# sensor_board_v0_53.net
KiCad netlist of a schematic drawn in EAGLE
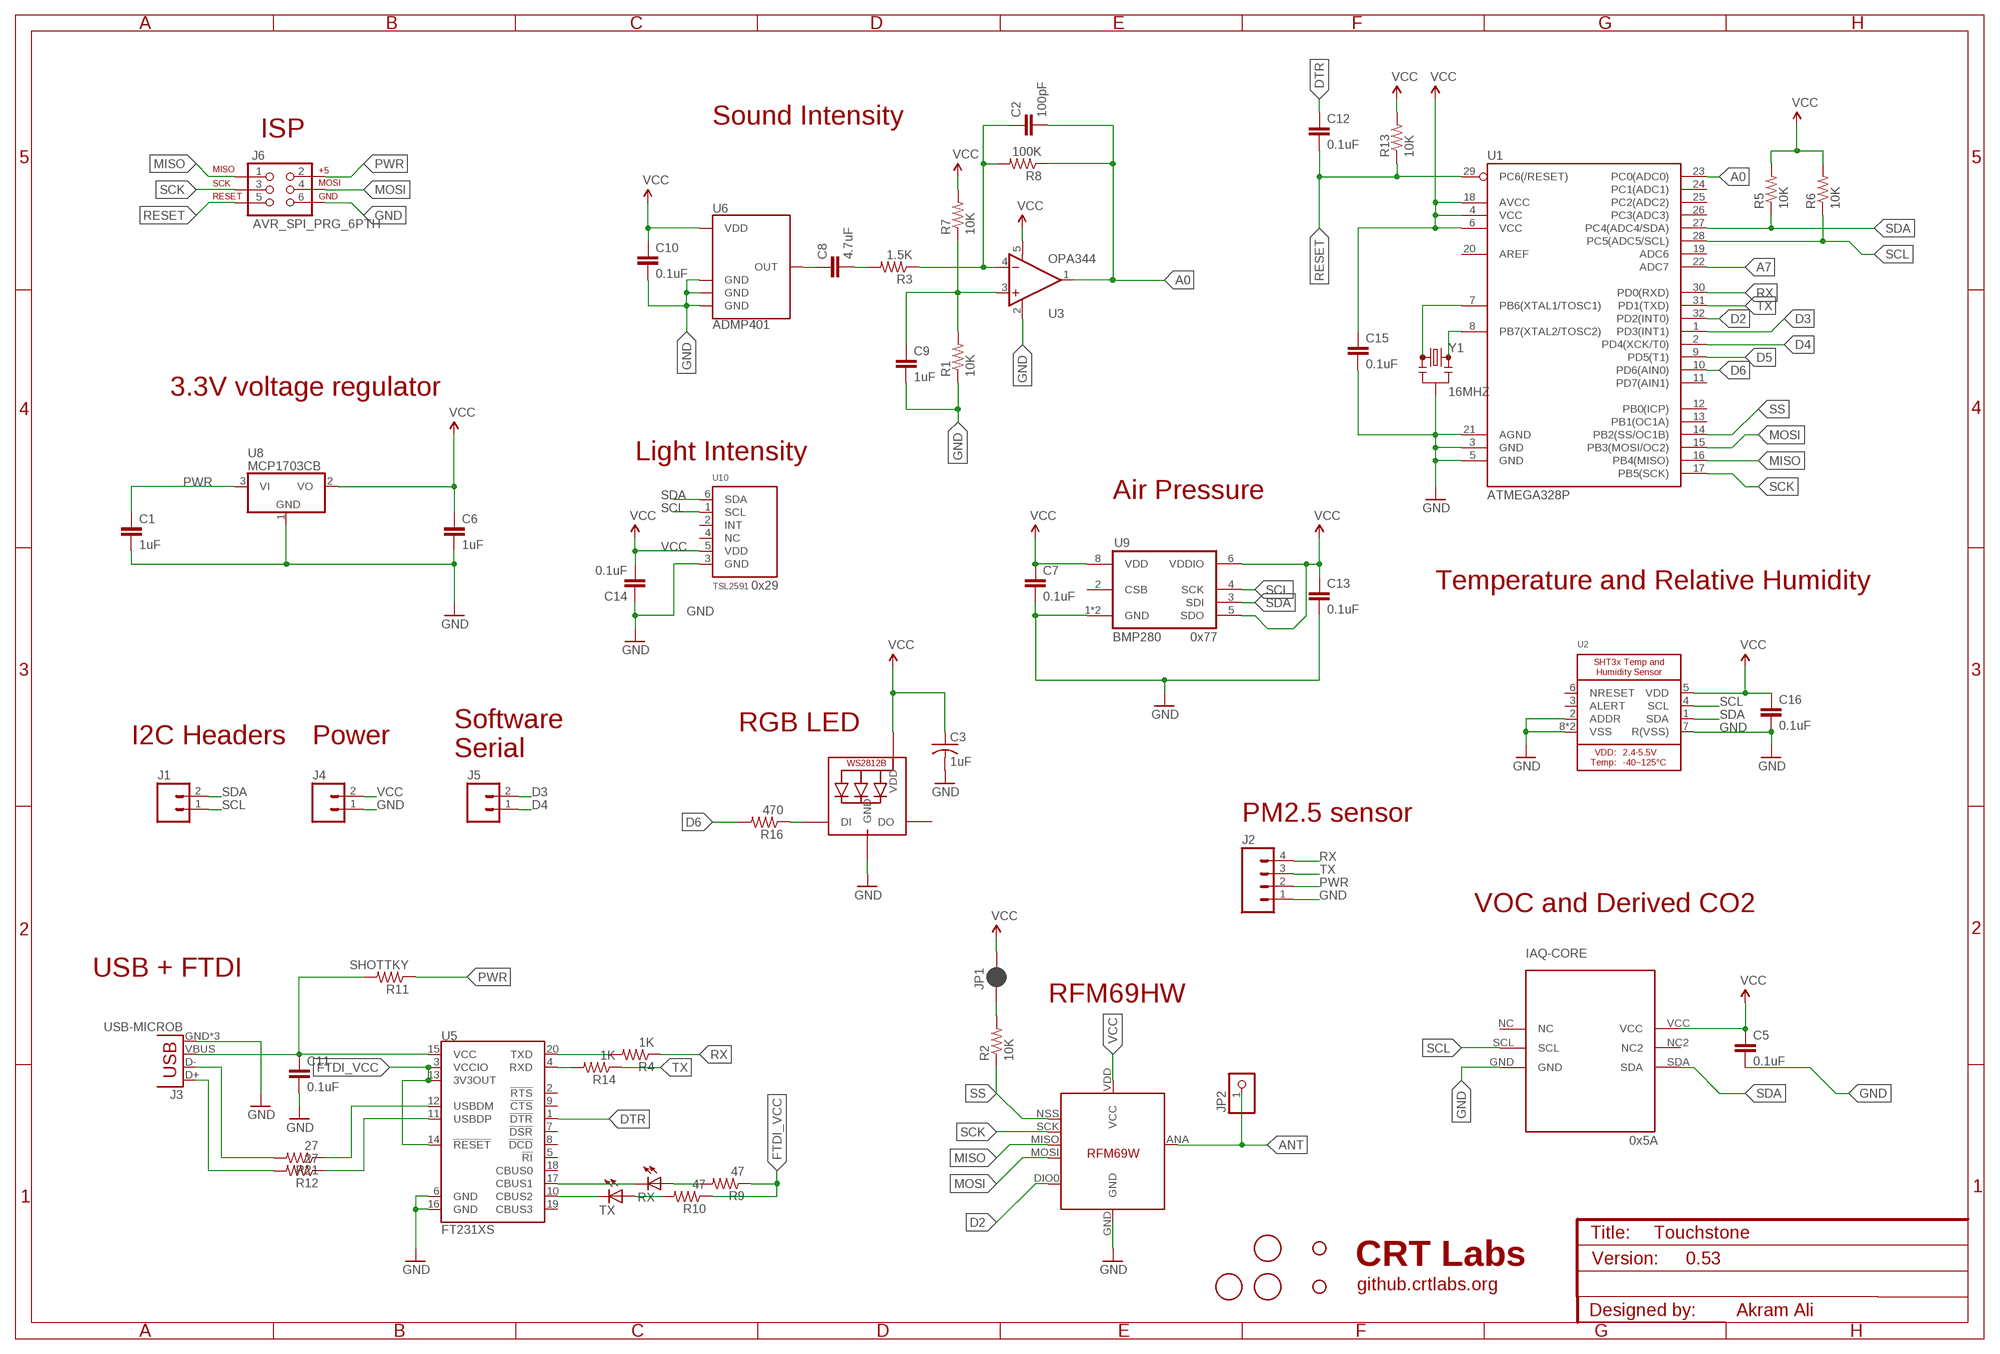
[diagram p0: schematic, sheet 1]

(export (version "E")
  (design (tool "Eeschema 10.0.6"))
  (components
    (comp (ref "C1")
      (value "1uF")
      (footprint "eagle-import:0805")
      (fields (field (name "MPN") "CC0805ZRY5V8BB105"))
      (libsource (lib "eagle-import") (part "CAP0805"))
    )
    (comp (ref "C2")
      (value "100pF")
      (footprint "eagle-import:0805")
      (fields (field (name "MPN") "CC0805JRNPOABN101"))
      (libsource (lib "eagle-import") (part "CAP0805"))
    )
    (comp (ref "C3")
      (value "1uF")
      (footprint "eagle-import:C0603K")
      (fields (field (name "MPN") "CC0805ZRY5V8BB105"))
      (libsource (lib "eagle-import") (part "C-USC0603K"))
    )
    (comp (ref "C5")
      (value "0.1uF")
      (footprint "eagle-import:0805")
      (fields (field (name "MPN") "CC0805KRX7R9BB104"))
      (libsource (lib "eagle-import") (part "SparkFun-Passives_CAP0805"))
    )
    (comp (ref "C6")
      (value "1uF")
      (footprint "eagle-import:0805")
      (fields (field (name "MPN") "CC0805ZRY5V8BB105"))
      (libsource (lib "eagle-import") (part "CAP0805"))
    )
    (comp (ref "C7")
      (value "0.1uF")
      (footprint "eagle-import:0805")
      (fields (field (name "MPN") "CC0805KRX7R9BB104"))
      (libsource (lib "eagle-import") (part "SparkFun-Passives_CAP0805"))
    )
    (comp (ref "C8")
      (value "4.7uF")
      (footprint "eagle-import:0805")
      (fields (field (name "MPN") "CC0805KKX7R6BB475"))
      (libsource (lib "eagle-import") (part "CAP0805"))
    )
    (comp (ref "C9")
      (value "1uF")
      (footprint "eagle-import:0805")
      (fields (field (name "MPN") "CC0805ZRY5V8BB105"))
      (libsource (lib "eagle-import") (part "CAP0805"))
    )
    (comp (ref "C10")
      (value "0.1uF")
      (footprint "eagle-import:0805")
      (fields (field (name "MPN") "CC0805KRX7R9BB104"))
      (libsource (lib "eagle-import") (part "CAP0805"))
    )
    (comp (ref "C11")
      (value "0.1uF")
      (footprint "eagle-import:0805")
      (fields (field (name "MPN") "CC0805KRX7R9BB104"))
      (libsource (lib "eagle-import") (part "CAP0805"))
    )
    (comp (ref "C12")
      (value "0.1uF")
      (footprint "eagle-import:0805")
      (fields (field (name "MPN") "CC0805KRX7R9BB104"))
      (libsource (lib "eagle-import") (part "SparkFun-Passives_CAP0805"))
    )
    (comp (ref "C13")
      (value "0.1uF")
      (footprint "eagle-import:0805")
      (fields (field (name "MPN") "CC0805KRX7R9BB104"))
      (libsource (lib "eagle-import") (part "SparkFun-Passives_CAP0805"))
    )
    (comp (ref "C14")
      (value "0.1uF")
      (footprint "eagle-import:0805")
      (fields (field (name "MPN") "CC0805KRX7R9BB104"))
      (libsource (lib "eagle-import") (part "SparkFun-Passives_CAP0805"))
    )
    (comp (ref "C15")
      (value "0.1uF")
      (footprint "eagle-import:0805")
      (fields (field (name "MPN") "CC0805KRX7R9BB104"))
      (libsource (lib "eagle-import") (part "SparkFun-Passives_CAP0805"))
    )
    (comp (ref "C16")
      (value "0.1uF")
      (footprint "eagle-import:0805")
      (fields (field (name "MPN") "CC0805KRX7R9BB104"))
      (libsource (lib "eagle-import") (part "SparkFun-Passives_CAP0805"))
    )
    (comp (ref "H1")
      (value "STAND-OFF")
      (footprint "eagle-import:STAND-OFF")
      (libsource (lib "eagle-import") (part "STAND-OFF"))
    )
    (comp (ref "H2")
      (value "STAND-OFF")
      (footprint "eagle-import:STAND-OFF")
      (libsource (lib "eagle-import") (part "STAND-OFF"))
    )
    (comp (ref "IAQ-CORE")
      (value "IAQ-CORE")
      (footprint "eagle-import:IAQ-CORE")
      (fields (field (name "MPN") "IAQ-CORE C"))
      (libsource (lib "eagle-import") (part "IAQ-CORE"))
    )
    (comp (ref "J1")
      (value "M02PTH")
      (footprint "eagle-import:1X02")
      (libsource (lib "eagle-import") (part "M02PTH"))
    )
    (comp (ref "J2")
      (value "M04PTH")
      (footprint "eagle-import:1X04")
      (libsource (lib "eagle-import") (part "M04PTH"))
    )
    (comp (ref "J3")
      (value "USB-MICROB")
      (footprint "eagle-import:USB-MICROB")
      (fields (field (name "MPN") "47346-0001"))
      (libsource (lib "eagle-import") (part "USB-MICROB"))
    )
    (comp (ref "J4")
      (value "M02PTH")
      (footprint "eagle-import:1X02")
      (libsource (lib "eagle-import") (part "M02PTH"))
    )
    (comp (ref "J5")
      (value "M02PTH")
      (footprint "eagle-import:1X02")
      (libsource (lib "eagle-import") (part "M02PTH"))
    )
    (comp (ref "J6")
      (value "AVR_SPI_PRG_6PTH")
      (footprint "eagle-import:2X3")
      (libsource (lib "eagle-import") (part "AVR_SPI_PRG_6PTH"))
    )
    (comp (ref "JP1")
      (value "JUMPER-PAD-2-NC_BY_PASTEFULL-BOX-SILK")
      (footprint "eagle-import:PAD-JUMPER-2-NC_BY_PASTE_YES_SILK_FULL_BOX")
      (libsource (lib "eagle-import") (part "JUMPER-PAD-2-NC_BY_PASTEFULL-BOX-SILK"))
    )
    (comp (ref "JP2")
      (value "PINHD-1X1")
      (footprint "eagle-import:1X01")
      (libsource (lib "eagle-import") (part "PINHD-1X1"))
    )
    (comp (ref "LED1")
      (value "WS2812B3535")
      (footprint "eagle-import:LED3535")
      (fields (field (name "MPN") "SK6812 mini"))
      (libsource (lib "eagle-import") (part "WS2812B3535"))
    )
    (comp (ref "R1")
      (value "10K")
      (footprint "eagle-import:0805")
      (fields (field (name "MPN") "RC0805FR-0710KL"))
      (libsource (lib "eagle-import") (part "RESISTOR0805-RES"))
    )
    (comp (ref "R2")
      (value "10K")
      (footprint "eagle-import:0805")
      (fields (field (name "MPN") "RC0805FR-0710KL"))
      (libsource (lib "eagle-import") (part "RESISTOR0805-RES"))
    )
    (comp (ref "R3")
      (value "1.5K")
      (footprint "eagle-import:0805")
      (fields (field (name "MPN") "RC0805FR-071K5L "))
      (libsource (lib "eagle-import") (part "RESISTOR0805-RES"))
    )
    (comp (ref "R4")
      (value "1K")
      (footprint "eagle-import:0805")
      (fields (field (name "MPN") "RC0805FR-071KL"))
      (libsource (lib "eagle-import") (part "RESISTOR0805-RES"))
    )
    (comp (ref "R5")
      (value "10K")
      (footprint "eagle-import:0805")
      (fields (field (name "MPN") "RC0805FR-0710KL"))
      (libsource (lib "eagle-import") (part "SparkFun-Resistors_RESISTOR0805-RES"))
    )
    (comp (ref "R6")
      (value "10K")
      (footprint "eagle-import:0805")
      (fields (field (name "MPN") "RC0805FR-0710KL"))
      (libsource (lib "eagle-import") (part "SparkFun-Resistors_RESISTOR0805-RES"))
    )
    (comp (ref "R7")
      (value "10K")
      (footprint "eagle-import:0805")
      (fields (field (name "MPN") "RC0805FR-0710KL"))
      (libsource (lib "eagle-import") (part "RESISTOR0805-RES"))
    )
    (comp (ref "R8")
      (value "100K")
      (footprint "eagle-import:0805")
      (fields (field (name "MPN") "RC0805FR-07100KL "))
      (libsource (lib "eagle-import") (part "RESISTOR0805-RES"))
    )
    (comp (ref "R9")
      (value "47")
      (footprint "eagle-import:0805")
      (fields (field (name "MPN") "RC0805FR-0747RL "))
      (libsource (lib "eagle-import") (part "RESISTOR0805-RES"))
    )
    (comp (ref "R10")
      (value "47")
      (footprint "eagle-import:0805")
      (fields (field (name "MPN") "RC0805FR-0747RL "))
      (libsource (lib "eagle-import") (part "RESISTOR0805-RES"))
    )
    (comp (ref "R11")
      (value "SHOTTKY")
      (footprint "eagle-import:0805")
      (fields (field (name "MPN") "SD0805S040S0R5"))
      (libsource (lib "eagle-import") (part "RESISTOR0805-RES"))
    )
    (comp (ref "R12")
      (value "27")
      (footprint "eagle-import:0805")
      (fields (field (name "MPN") "RC0805FR-0727RL "))
      (libsource (lib "eagle-import") (part "RESISTOR0805-RES"))
    )
    (comp (ref "R13")
      (value "10K")
      (footprint "eagle-import:0805")
      (fields (field (name "MPN") "RC0805FR-0710KL"))
      (libsource (lib "eagle-import") (part "RESISTOR0805-RES"))
    )
    (comp (ref "R14")
      (value "1K")
      (footprint "eagle-import:0805")
      (fields (field (name "MPN") "RC0805FR-071KL"))
      (libsource (lib "eagle-import") (part "RESISTOR0805-RES"))
    )
    (comp (ref "R16")
      (value "470")
      (footprint "eagle-import:R0603")
      (fields (field (name "MPN") "RC0805FR-07470RL "))
      (libsource (lib "eagle-import") (part "R-US_R0603"))
    )
    (comp (ref "R21")
      (value "27")
      (footprint "eagle-import:0805")
      (fields (field (name "MPN") "RC0805FR-0727RL "))
      (libsource (lib "eagle-import") (part "RESISTOR0805-RES"))
    )
    (comp (ref "RX")
      (value "LEDCHIPLED_0805")
      (footprint "eagle-import:CHIPLED_0805")
      (fields (field (name "MPN") "LG R971-KN-1"))
      (libsource (lib "eagle-import") (part "LEDCHIPLED_0805"))
    )
    (comp (ref "TX")
      (value "LEDCHIPLED_0805")
      (footprint "eagle-import:CHIPLED_0805")
      (fields (field (name "MPN") "LG R971-KN-1"))
      (libsource (lib "eagle-import") (part "LEDCHIPLED_0805"))
    )
    (comp (ref "U$1")
      (value "FIDUCIAL")
      (footprint "eagle-import:FIDUCIAL_1MM")
      (libsource (lib "eagle-import") (part "FIDUCIAL"))
    )
    (comp (ref "U$2")
      (value "FIDUCIAL")
      (footprint "eagle-import:FIDUCIAL_1MM")
      (libsource (lib "eagle-import") (part "FIDUCIAL"))
    )
    (comp (ref "U$3")
      (value "FIDUCIAL")
      (footprint "eagle-import:FIDUCIAL_1MM")
      (libsource (lib "eagle-import") (part "FIDUCIAL"))
    )
    (comp (ref "U1")
      (value "ATMEGA328P")
      (footprint "eagle-import:TQFP32-08")
      (fields (field (name "MPN") "ATMEGA328PB-AU"))
      (libsource (lib "eagle-import") (part "ATMEGA328P_TQFP"))
    )
    (comp (ref "U2")
      (value "SHT3X")
      (footprint "eagle-import:SHT3X")
      (fields (field (name "MPN") "SHT35-DIS-B"))
      (libsource (lib "eagle-import") (part "SHT3X"))
    )
    (comp (ref "U3")
      (value "OPA344")
      (footprint "eagle-import:SOT23-5")
      (fields (field (name "MPN") "OPA344NA/3K"))
      (libsource (lib "eagle-import") (part "OPA344"))
    )
    (comp (ref "U4")
      (value "RFM69HW")
      (footprint "eagle-import:LOWPOWERLAB_RFM69W-MINPADS")
      (libsource (lib "eagle-import") (part "LOWPOWERLAB_RFM69"))
    )
    (comp (ref "U5")
      (value "FT231XS")
      (footprint "eagle-import:SSOP20_L")
      (fields (field (name "MPN") "FT231XQ-R"))
      (libsource (lib "eagle-import") (part "FT231XS"))
    )
    (comp (ref "U6")
      (value "ADMP401")
      (footprint "eagle-import:ADMP401")
      (fields (field (name "MPN") "INMP401ACEZ-R7"))
      (libsource (lib "eagle-import") (part "ADMP401"))
    )
    (comp (ref "U8")
      (value "MCP1703CB")
      (footprint "eagle-import:SOT23")
      (fields (field (name "MPN") "MCP1703T-2502E/CB"))
      (libsource (lib "eagle-import") (part "MCP1703CB"))
    )
    (comp (ref "U9")
      (value "BMP280")
      (footprint "eagle-import:BMP280")
      (libsource (lib "eagle-import") (part "BMP280"))
    )
    (comp (ref "U10")
      (value "TSL2591")
      (footprint "eagle-import:DFN6_TAOS")
      (fields (field (name "MPN") "TSL25911FN "))
      (libsource (lib "eagle-import") (part "LIGHT_TSL2591"))
    )
    (comp (ref "Y1")
      (value "16MHZ")
      (footprint "eagle-import:RESONATOR-SMD")
      (fields (field (name "MPN") "CSTCE16M0V53-R0"))
      (libsource (lib "eagle-import") (part "RESONATOR16MHZ"))
    )
  )
  (nets
    (net (code "1") (name "A0") (class "Default")
      (node (ref "C2") (pin "2") (pinfunction "2_2") (pintype "passive"))
      (node (ref "R8") (pin "1") (pinfunction "1_1") (pintype "passive"))
      (node (ref "U1") (pin "23") (pinfunction "PC0(ADC0)_23") (pintype "bidirectional"))
      (node (ref "U3") (pin "1") (pinfunction "OUT_1") (pintype "output"))
    )
    (net (code "2") (name "A7") (class "Default")
      (node (ref "U1") (pin "22") (pinfunction "ADC7_22") (pintype "bidirectional"))
    )
    (net (code "3") (name "ANT") (class "Default")
      (node (ref "JP2") (pin "1") (pinfunction "1_1") (pintype "passive"))
      (node (ref "U4") (pin "ANA") (pinfunction "ANT_ANA") (pintype "passive"))
    )
    (net (code "4") (name "D2") (class "Default")
      (node (ref "U1") (pin "32") (pinfunction "PD2(INT0)_32") (pintype "bidirectional"))
      (node (ref "U4") (pin "DIO0") (pinfunction "DIO0_DIO0") (pintype "open_collector"))
    )
    (net (code "5") (name "D3") (class "Default")
      (node (ref "J5") (pin "2") (pinfunction "2_2") (pintype "passive"))
      (node (ref "U1") (pin "1") (pinfunction "PD3(INT1)_1") (pintype "bidirectional"))
    )
    (net (code "6") (name "D4") (class "Default")
      (node (ref "J5") (pin "1") (pinfunction "1_1") (pintype "passive"))
      (node (ref "U1") (pin "2") (pinfunction "PD4(XCK/T0)_2") (pintype "bidirectional"))
    )
    (net (code "7") (name "D5") (class "Default")
      (node (ref "U1") (pin "9") (pinfunction "PD5(T1)_9") (pintype "bidirectional"))
    )
    (net (code "8") (name "D6") (class "Default")
      (node (ref "R16") (pin "2") (pinfunction "2_2") (pintype "passive"))
      (node (ref "U1") (pin "10") (pinfunction "PD6(AIN0)_10") (pintype "bidirectional"))
    )
    (net (code "9") (name "DTR") (class "Default")
      (node (ref "C12") (pin "1") (pinfunction "1_1") (pintype "passive"))
      (node (ref "U5") (pin "1") (pinfunction "~{DTR}_1") (pintype "bidirectional"))
    )
    (net (code "10") (name "FTDI_VCC") (class "Default")
      (node (ref "R10") (pin "1") (pinfunction "1_1") (pintype "passive"))
      (node (ref "R9") (pin "1") (pinfunction "1_1") (pintype "passive"))
      (node (ref "U5") (pin "13") (pinfunction "3V3OUT_13") (pintype "bidirectional"))
      (node (ref "U5") (pin "14") (pinfunction "~{RESET}_14") (pintype "bidirectional"))
      (node (ref "U5") (pin "3") (pinfunction "VCCIO_3") (pintype "bidirectional"))
    )
    (net (code "11") (name "GND") (class "Default")
      (node (ref "C1") (pin "2") (pinfunction "2_2") (pintype "passive"))
      (node (ref "C10") (pin "2") (pinfunction "2_2") (pintype "passive"))
      (node (ref "C11") (pin "2") (pinfunction "2_2") (pintype "passive"))
      (node (ref "C13") (pin "2") (pinfunction "2_2") (pintype "passive"))
      (node (ref "C14") (pin "1") (pinfunction "1_1") (pintype "passive"))
      (node (ref "C15") (pin "2") (pinfunction "2_2") (pintype "passive"))
      (node (ref "C16") (pin "2") (pinfunction "2_2") (pintype "passive"))
      (node (ref "C3") (pin "2") (pinfunction "2_2") (pintype "passive"))
      (node (ref "C5") (pin "2") (pinfunction "2_2") (pintype "passive"))
      (node (ref "C6") (pin "2") (pinfunction "2_2") (pintype "passive"))
      (node (ref "C7") (pin "2") (pinfunction "2_2") (pintype "passive"))
      (node (ref "C9") (pin "2") (pinfunction "2_2") (pintype "passive"))
      (node (ref "IAQ-CORE") (pin "GND") (pinfunction "GND_GND") (pintype "bidirectional"))
      (node (ref "J2") (pin "1") (pinfunction "1_1") (pintype "passive"))
      (node (ref "J3") (pin "GND") (pinfunction "GND_GND") (pintype "bidirectional"))
      (node (ref "J3") (pin "MT1") (pinfunction "GND_MT1") (pintype "bidirectional"))
      (node (ref "J3") (pin "MT2") (pinfunction "GND_MT2") (pintype "bidirectional"))
      (node (ref "J4") (pin "1") (pinfunction "1_1") (pintype "passive"))
      (node (ref "J6") (pin "6") (pinfunction "6_6") (pintype "passive"))
      (node (ref "LED1") (pin "4") (pinfunction "GND_4") (pintype "power_in"))
      (node (ref "R1") (pin "1") (pinfunction "1_1") (pintype "passive"))
      (node (ref "U1") (pin "21") (pinfunction "AGND_21") (pintype "bidirectional"))
      (node (ref "U1") (pin "3") (pinfunction "GND_3") (pintype "bidirectional"))
      (node (ref "U1") (pin "5") (pinfunction "GND_5") (pintype "bidirectional"))
      (node (ref "U10") (pin "3") (pinfunction "GND_3") (pintype "power_in"))
      (node (ref "U2") (pin "2") (pinfunction "ADDR_2") (pintype "bidirectional"))
      (node (ref "U2") (pin "7") (pinfunction "R(VSS)_7") (pintype "bidirectional"))
      (node (ref "U2") (pin "8") (pinfunction "VSS_8") (pintype "power_in"))
      (node (ref "U2") (pin "THERMAL") (pinfunction "VSS_THERMAL") (pintype "power_in"))
      (node (ref "U3") (pin "2") (pinfunction "V-_2") (pintype "power_in"))
      (node (ref "U4") (pin "GND") (pinfunction "GND_GND") (pintype "power_in"))
      (node (ref "U5") (pin "16") (pinfunction "GND_16") (pintype "bidirectional"))
      (node (ref "U5") (pin "6") (pinfunction "GND_6") (pintype "bidirectional"))
      (node (ref "U6") (pin "2") (pinfunction "GND_2") (pintype "bidirectional"))
      (node (ref "U6") (pin "4") (pinfunction "GND_4") (pintype "bidirectional"))
      (node (ref "U6") (pin "6") (pinfunction "GND_6") (pintype "bidirectional"))
      (node (ref "U8") (pin "1") (pinfunction "GND_1") (pintype "passive"))
      (node (ref "U9") (pin "1") (pinfunction "GND_1") (pintype "power_in"))
      (node (ref "U9") (pin "7") (pinfunction "GND_7") (pintype "power_in"))
      (node (ref "Y1") (pin "2") (pinfunction "2_2") (pintype "passive"))
    )
    (net (code "12") (name "MISO") (class "Default")
      (node (ref "J6") (pin "1") (pinfunction "1_1") (pintype "passive"))
      (node (ref "U1") (pin "16") (pinfunction "PB4(MISO)_16") (pintype "bidirectional"))
      (node (ref "U4") (pin "MISO") (pinfunction "MISO_MISO") (pintype "input"))
    )
    (net (code "13") (name "MOSI") (class "Default")
      (node (ref "J6") (pin "4") (pinfunction "4_4") (pintype "passive"))
      (node (ref "U1") (pin "15") (pinfunction "PB3(MOSI/OC2)_15") (pintype "bidirectional"))
      (node (ref "U4") (pin "MOSI") (pinfunction "MOSI_MOSI") (pintype "output"))
    )
    (net (code "14") (name "Net-(C8-Pad2)") (class "Default")
      (node (ref "C8") (pin "2") (pinfunction "2_2") (pintype "passive"))
      (node (ref "R3") (pin "2") (pinfunction "2_2") (pintype "passive"))
    )
    (net (code "15") (name "Net-(J3-PadD+)") (class "Default")
      (node (ref "J3") (pin "D+") (pinfunction "D+_D+") (pintype "bidirectional"))
      (node (ref "R12") (pin "2") (pinfunction "2_2") (pintype "passive"))
    )
    (net (code "16") (name "Net-(J3-PadD-)") (class "Default")
      (node (ref "J3") (pin "D-") (pinfunction "D-_D-") (pintype "bidirectional"))
      (node (ref "R21") (pin "2") (pinfunction "2_2") (pintype "passive"))
    )
    (net (code "17") (name "Net-(JP1-Pad1)") (class "Default")
      (node (ref "JP1") (pin "1") (pinfunction "1_1") (pintype "passive"))
      (node (ref "R2") (pin "2") (pinfunction "2_2") (pintype "passive"))
    )
    (net (code "18") (name "Net-(LED1-DI)") (class "Default")
      (node (ref "LED1") (pin "1") (pinfunction "DI_1") (pintype "input"))
      (node (ref "R16") (pin "1") (pinfunction "1_1") (pintype "passive"))
    )
    (net (code "19") (name "Net-(R9-Pad2)") (class "Default")
      (node (ref "R9") (pin "2") (pinfunction "2_2") (pintype "passive"))
      (node (ref "RX") (pin "A") (pinfunction "A_A") (pintype "passive"))
    )
    (net (code "20") (name "Net-(R10-Pad2)") (class "Default")
      (node (ref "R10") (pin "2") (pinfunction "2_2") (pintype "passive"))
      (node (ref "TX") (pin "A") (pinfunction "A_A") (pintype "passive"))
    )
    (net (code "21") (name "Net-(U1-PB6(XTAL1{slash}TOSC1))") (class "Default")
      (node (ref "U1") (pin "7") (pinfunction "PB6(XTAL1/TOSC1)_7") (pintype "bidirectional"))
      (node (ref "Y1") (pin "1") (pinfunction "1_1") (pintype "passive"))
    )
    (net (code "22") (name "Net-(U1-PB7(XTAL2{slash}TOSC2))") (class "Default")
      (node (ref "U1") (pin "8") (pinfunction "PB7(XTAL2/TOSC2)_8") (pintype "bidirectional"))
      (node (ref "Y1") (pin "3") (pinfunction "3_3") (pintype "passive"))
    )
    (net (code "23") (name "Net-(U3-+IN)") (class "Default")
      (node (ref "C9") (pin "1") (pinfunction "1_1") (pintype "passive"))
      (node (ref "R1") (pin "2") (pinfunction "2_2") (pintype "passive"))
      (node (ref "R7") (pin "1") (pinfunction "1_1") (pintype "passive"))
      (node (ref "U3") (pin "3") (pinfunction "+IN_3") (pintype "input"))
    )
    (net (code "24") (name "Net-(U3--IN)") (class "Default")
      (node (ref "C2") (pin "1") (pinfunction "1_1") (pintype "passive"))
      (node (ref "R3") (pin "1") (pinfunction "1_1") (pintype "passive"))
      (node (ref "R8") (pin "2") (pinfunction "2_2") (pintype "passive"))
      (node (ref "U3") (pin "4") (pinfunction "-IN_4") (pintype "input"))
    )
    (net (code "25") (name "Net-(U5-CBUS1)") (class "Default")
      (node (ref "RX") (pin "C") (pinfunction "C_C") (pintype "passive"))
      (node (ref "U5") (pin "17") (pinfunction "CBUS1_17") (pintype "bidirectional"))
    )
    (net (code "26") (name "Net-(U5-CBUS2)") (class "Default")
      (node (ref "TX") (pin "C") (pinfunction "C_C") (pintype "passive"))
      (node (ref "U5") (pin "10") (pinfunction "CBUS2_10") (pintype "bidirectional"))
    )
    (net (code "27") (name "Net-(U5-RXD)") (class "Default")
      (node (ref "R14") (pin "2") (pinfunction "2_2") (pintype "passive"))
      (node (ref "U5") (pin "4") (pinfunction "RXD_4") (pintype "bidirectional"))
    )
    (net (code "28") (name "Net-(U5-TXD)") (class "Default")
      (node (ref "R4") (pin "2") (pinfunction "2_2") (pintype "passive"))
      (node (ref "U5") (pin "20") (pinfunction "TXD_20") (pintype "bidirectional"))
    )
    (net (code "29") (name "Net-(U5-USBDM)") (class "Default")
      (node (ref "R21") (pin "1") (pinfunction "1_1") (pintype "passive"))
      (node (ref "U5") (pin "12") (pinfunction "USBDM_12") (pintype "bidirectional"))
    )
    (net (code "30") (name "Net-(U5-USBDP)") (class "Default")
      (node (ref "R12") (pin "1") (pinfunction "1_1") (pintype "passive"))
      (node (ref "U5") (pin "11") (pinfunction "USBDP_11") (pintype "bidirectional"))
    )
    (net (code "31") (name "Net-(U5-VCC)") (class "Default")
      (node (ref "C11") (pin "1") (pinfunction "1_1") (pintype "passive"))
      (node (ref "J3") (pin "VBUS") (pinfunction "VBUS_VBUS") (pintype "bidirectional"))
      (node (ref "R11") (pin "2") (pinfunction "2_2") (pintype "passive"))
      (node (ref "U5") (pin "15") (pinfunction "VCC_15") (pintype "bidirectional"))
    )
    (net (code "32") (name "Net-(U6-OUT)") (class "Default")
      (node (ref "C8") (pin "1") (pinfunction "1_1") (pintype "passive"))
      (node (ref "U6") (pin "1") (pinfunction "OUT_1") (pintype "bidirectional"))
    )
    (net (code "33") (name "PWR") (class "Default")
      (node (ref "C1") (pin "1") (pinfunction "1_1") (pintype "passive"))
      (node (ref "J2") (pin "2") (pinfunction "2_2") (pintype "passive"))
      (node (ref "J6") (pin "2") (pinfunction "2_2") (pintype "passive"))
      (node (ref "R11") (pin "1") (pinfunction "1_1") (pintype "passive"))
      (node (ref "U8") (pin "3") (pinfunction "VI_3") (pintype "input"))
    )
    (net (code "34") (name "RESET") (class "Default")
      (node (ref "C12") (pin "2") (pinfunction "2_2") (pintype "passive"))
      (node (ref "J6") (pin "5") (pinfunction "5_5") (pintype "passive"))
      (node (ref "R13") (pin "1") (pinfunction "1_1") (pintype "passive"))
      (node (ref "U1") (pin "29") (pinfunction "PC6(/RESET)_29") (pintype "bidirectional"))
    )
    (net (code "35") (name "RX") (class "Default")
      (node (ref "J2") (pin "4") (pinfunction "4_4") (pintype "passive"))
      (node (ref "R4") (pin "1") (pinfunction "1_1") (pintype "passive"))
      (node (ref "U1") (pin "30") (pinfunction "PD0(RXD)_30") (pintype "bidirectional"))
    )
    (net (code "36") (name "SCK") (class "Default")
      (node (ref "J6") (pin "3") (pinfunction "3_3") (pintype "passive"))
      (node (ref "U1") (pin "17") (pinfunction "PB5(SCK)_17") (pintype "bidirectional"))
      (node (ref "U4") (pin "SCK") (pinfunction "SCK_SCK") (pintype "input"))
    )
    (net (code "37") (name "SCL") (class "Default")
      (node (ref "IAQ-CORE") (pin "SCL") (pinfunction "SCL_SCL") (pintype "bidirectional"))
      (node (ref "J1") (pin "1") (pinfunction "1_1") (pintype "passive"))
      (node (ref "R6") (pin "1") (pinfunction "1_1") (pintype "passive"))
      (node (ref "U1") (pin "28") (pinfunction "PC5(ADC5/SCL)_28") (pintype "bidirectional"))
      (node (ref "U10") (pin "1") (pinfunction "SCL_1") (pintype "bidirectional"))
      (node (ref "U2") (pin "4") (pinfunction "SCL_4") (pintype "bidirectional"))
      (node (ref "U9") (pin "4") (pinfunction "SCK_4") (pintype "bidirectional"))
    )
    (net (code "38") (name "SDA") (class "Default")
      (node (ref "IAQ-CORE") (pin "SDA") (pinfunction "SDA_SDA") (pintype "bidirectional"))
      (node (ref "J1") (pin "2") (pinfunction "2_2") (pintype "passive"))
      (node (ref "R5") (pin "1") (pinfunction "1_1") (pintype "passive"))
      (node (ref "U1") (pin "27") (pinfunction "PC4(ADC4/SDA)_27") (pintype "bidirectional"))
      (node (ref "U10") (pin "6") (pinfunction "SDA_6") (pintype "bidirectional"))
      (node (ref "U2") (pin "1") (pinfunction "SDA_1") (pintype "bidirectional"))
      (node (ref "U9") (pin "3") (pinfunction "SDI_3") (pintype "bidirectional"))
    )
    (net (code "39") (name "SS") (class "Default")
      (node (ref "R2") (pin "1") (pinfunction "1_1") (pintype "passive"))
      (node (ref "U1") (pin "14") (pinfunction "PB2(SS/OC1B)_14") (pintype "bidirectional"))
      (node (ref "U4") (pin "NSS") (pinfunction "SEL_NSS") (pintype "input"))
    )
    (net (code "40") (name "TX") (class "Default")
      (node (ref "J2") (pin "3") (pinfunction "3_3") (pintype "passive"))
      (node (ref "R14") (pin "1") (pinfunction "1_1") (pintype "passive"))
      (node (ref "U1") (pin "31") (pinfunction "PD1(TXD)_31") (pintype "bidirectional"))
    )
    (net (code "41") (name "VCC") (class "Default")
      (node (ref "C10") (pin "1") (pinfunction "1_1") (pintype "passive"))
      (node (ref "C13") (pin "1") (pinfunction "1_1") (pintype "passive"))
      (node (ref "C14") (pin "2") (pinfunction "2_2") (pintype "passive"))
      (node (ref "C15") (pin "1") (pinfunction "1_1") (pintype "passive"))
      (node (ref "C16") (pin "1") (pinfunction "1_1") (pintype "passive"))
      (node (ref "C3") (pin "1") (pinfunction "1_1") (pintype "passive"))
      (node (ref "C5") (pin "1") (pinfunction "1_1") (pintype "passive"))
      (node (ref "C6") (pin "1") (pinfunction "1_1") (pintype "passive"))
      (node (ref "C7") (pin "1") (pinfunction "1_1") (pintype "passive"))
      (node (ref "IAQ-CORE") (pin "VCC") (pinfunction "VCC_VCC") (pintype "bidirectional"))
      (node (ref "J4") (pin "2") (pinfunction "2_2") (pintype "passive"))
      (node (ref "JP1") (pin "2") (pinfunction "2_2") (pintype "passive"))
      (node (ref "LED1") (pin "2") (pinfunction "VDD_2") (pintype "power_in"))
      (node (ref "R13") (pin "2") (pinfunction "2_2") (pintype "passive"))
      (node (ref "R5") (pin "2") (pinfunction "2_2") (pintype "passive"))
      (node (ref "R6") (pin "2") (pinfunction "2_2") (pintype "passive"))
      (node (ref "R7") (pin "2") (pinfunction "2_2") (pintype "passive"))
      (node (ref "U1") (pin "18") (pinfunction "AVCC_18") (pintype "bidirectional"))
      (node (ref "U1") (pin "4") (pinfunction "VCC_4") (pintype "bidirectional"))
      (node (ref "U1") (pin "6") (pinfunction "VCC_6") (pintype "bidirectional"))
      (node (ref "U10") (pin "5") (pinfunction "VDD_5") (pintype "power_in"))
      (node (ref "U2") (pin "5") (pinfunction "VDD_5") (pintype "power_in"))
      (node (ref "U3") (pin "5") (pinfunction "V+_5") (pintype "power_in"))
      (node (ref "U4") (pin "VDD") (pinfunction "VCC_VDD") (pintype "power_in"))
      (node (ref "U6") (pin "5") (pinfunction "VDD_5") (pintype "bidirectional"))
      (node (ref "U8") (pin "2") (pinfunction "VO_2") (pintype "passive"))
      (node (ref "U9") (pin "5") (pinfunction "SDO_5") (pintype "input"))
      (node (ref "U9") (pin "6") (pinfunction "VDDIO_6") (pintype "power_in"))
      (node (ref "U9") (pin "8") (pinfunction "VDD_8") (pintype "power_in"))
    )
    (net (code "42") (name "unconnected-(IAQ-CORE-PadNC)") (class "Default")
      (node (ref "IAQ-CORE") (pin "NC") (pinfunction "NC_NC") (pintype "bidirectional"))
    )
    (net (code "43") (name "unconnected-(IAQ-CORE-PadNC2)") (class "Default")
      (node (ref "IAQ-CORE") (pin "NC2") (pinfunction "NC2_NC2") (pintype "bidirectional"))
    )
    (net (code "44") (name "unconnected-(LED1-DO-Pad3)") (class "Default")
      (node (ref "LED1") (pin "3") (pinfunction "DO_3") (pintype "output"))
    )
    (net (code "45") (name "unconnected-(U1-ADC6-Pad19)") (class "Default")
      (node (ref "U1") (pin "19") (pinfunction "ADC6_19") (pintype "bidirectional"))
    )
    (net (code "46") (name "unconnected-(U1-AREF-Pad20)") (class "Default")
      (node (ref "U1") (pin "20") (pinfunction "AREF_20") (pintype "bidirectional"))
    )
    (net (code "47") (name "unconnected-(U1-PB0(ICP)-Pad12)") (class "Default")
      (node (ref "U1") (pin "12") (pinfunction "PB0(ICP)_12") (pintype "bidirectional"))
    )
    (net (code "48") (name "unconnected-(U1-PB1(OC1A)-Pad13)") (class "Default")
      (node (ref "U1") (pin "13") (pinfunction "PB1(OC1A)_13") (pintype "bidirectional"))
    )
    (net (code "49") (name "unconnected-(U1-PC1(ADC1)-Pad24)") (class "Default")
      (node (ref "U1") (pin "24") (pinfunction "PC1(ADC1)_24") (pintype "bidirectional"))
    )
    (net (code "50") (name "unconnected-(U1-PC2(ADC2)-Pad25)") (class "Default")
      (node (ref "U1") (pin "25") (pinfunction "PC2(ADC2)_25") (pintype "bidirectional"))
    )
    (net (code "51") (name "unconnected-(U1-PC3(ADC3)-Pad26)") (class "Default")
      (node (ref "U1") (pin "26") (pinfunction "PC3(ADC3)_26") (pintype "bidirectional"))
    )
    (net (code "52") (name "unconnected-(U1-PD7(AIN1)-Pad11)") (class "Default")
      (node (ref "U1") (pin "11") (pinfunction "PD7(AIN1)_11") (pintype "bidirectional"))
    )
    (net (code "53") (name "unconnected-(U2-ALERT-Pad3)") (class "Default")
      (node (ref "U2") (pin "3") (pinfunction "ALERT_3") (pintype "bidirectional"))
    )
    (net (code "54") (name "unconnected-(U2-NRESET-Pad6)") (class "Default")
      (node (ref "U2") (pin "6") (pinfunction "NRESET_6") (pintype "bidirectional"))
    )
    (net (code "55") (name "unconnected-(U5-CBUS0-Pad18)") (class "Default")
      (node (ref "U5") (pin "18") (pinfunction "CBUS0_18") (pintype "bidirectional"))
    )
    (net (code "56") (name "unconnected-(U5-CBUS3-Pad19)") (class "Default")
      (node (ref "U5") (pin "19") (pinfunction "CBUS3_19") (pintype "bidirectional"))
    )
    (net (code "57") (name "unconnected-(U5-~{CTS}-Pad9)") (class "Default")
      (node (ref "U5") (pin "9") (pinfunction "~{CTS}_9") (pintype "bidirectional"))
    )
    (net (code "58") (name "unconnected-(U5-~{DCD}-Pad8)") (class "Default")
      (node (ref "U5") (pin "8") (pinfunction "~{DCD}_8") (pintype "bidirectional"))
    )
    (net (code "59") (name "unconnected-(U5-~{DSR}-Pad7)") (class "Default")
      (node (ref "U5") (pin "7") (pinfunction "~{DSR}_7") (pintype "bidirectional"))
    )
    (net (code "60") (name "unconnected-(U5-~{RI}-Pad5)") (class "Default")
      (node (ref "U5") (pin "5") (pinfunction "~{RI}_5") (pintype "bidirectional"))
    )
    (net (code "61") (name "unconnected-(U5-~{RTS}-Pad2)") (class "Default")
      (node (ref "U5") (pin "2") (pinfunction "~{RTS}_2") (pintype "bidirectional"))
    )
    (net (code "62") (name "unconnected-(U9-CSB-Pad2)") (class "Default")
      (node (ref "U9") (pin "2") (pinfunction "CSB_2") (pintype "input"))
    )
    (net (code "63") (name "unconnected-(U10-INT-Pad2)") (class "Default")
      (node (ref "U10") (pin "2") (pinfunction "INT_2") (pintype "output"))
    )
    (net (code "64") (name "unconnected-(U10-NC-Pad4)") (class "Default")
      (node (ref "U10") (pin "4") (pinfunction "NC_4") (pintype "no_connect"))
    )
  )
)
